# nRF24L01-Chip-v12.net
KiCad netlist of a schematic drawn in EAGLE
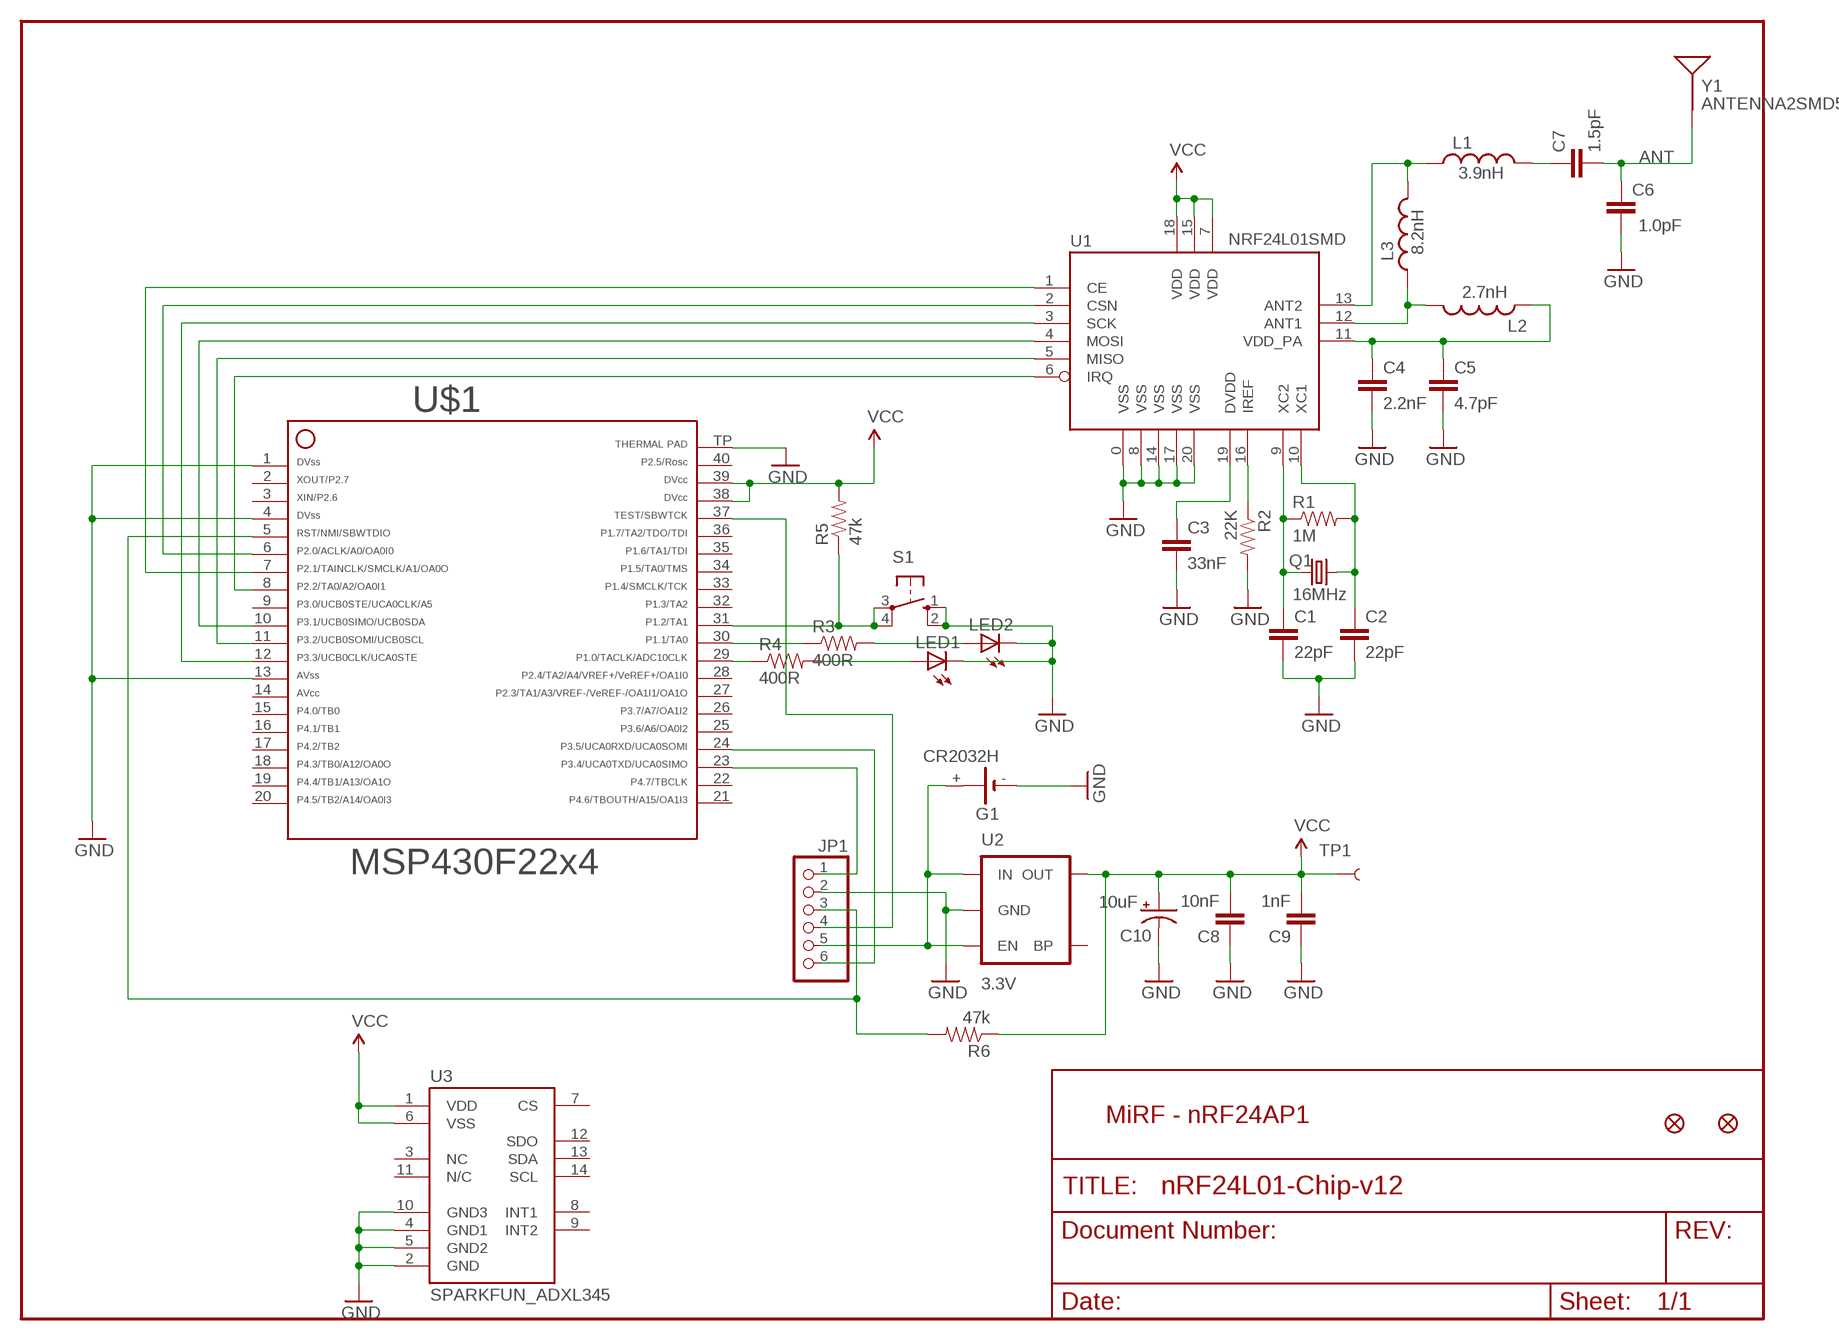
[diagram p0: schematic, sheet 1]

(export (version "E")
  (design (tool "Eeschema 10.0.6"))
  (components
    (comp (ref "C1")
      (value "22pF")
      (footprint "eagle-import:C0402")
      (libsource (lib "eagle-import") (part "CAP0402"))
    )
    (comp (ref "C2")
      (value "22pF")
      (footprint "eagle-import:C0402")
      (libsource (lib "eagle-import") (part "CAP0402"))
    )
    (comp (ref "C3")
      (value "33nF")
      (footprint "eagle-import:C0402")
      (libsource (lib "eagle-import") (part "CAP0402"))
    )
    (comp (ref "C4")
      (value "2.2nF")
      (footprint "eagle-import:C0402")
      (libsource (lib "eagle-import") (part "CAP0402"))
    )
    (comp (ref "C5")
      (value "4.7pF")
      (footprint "eagle-import:C0402")
      (libsource (lib "eagle-import") (part "CAP0402"))
    )
    (comp (ref "C6")
      (value "1.0pF")
      (footprint "eagle-import:C0402")
      (libsource (lib "eagle-import") (part "CAP0402"))
    )
    (comp (ref "C7")
      (value "1.5pF")
      (footprint "eagle-import:C0402")
      (libsource (lib "eagle-import") (part "CAP0402"))
    )
    (comp (ref "C8")
      (value "10nF")
      (footprint "eagle-import:C0402")
      (libsource (lib "eagle-import") (part "CAP0402"))
    )
    (comp (ref "C9")
      (value "1nF")
      (footprint "eagle-import:C0402")
      (libsource (lib "eagle-import") (part "CAP0402"))
    )
    (comp (ref "C10")
      (value "10uF")
      (footprint "eagle-import:EIA3216")
      (libsource (lib "eagle-import") (part "CAP_POL1206"))
    )
    (comp (ref "G1")
      (value "CR2032H")
      (footprint "eagle-import:CR2032H")
      (libsource (lib "eagle-import") (part "CR2032H"))
    )
    (comp (ref "JP1")
      (value "PINHD-1X6")
      (footprint "eagle-import:1X06")
      (libsource (lib "eagle-import") (part "PINHD-1X6"))
    )
    (comp (ref "L1")
      (value "3.9nH")
      (footprint "eagle-import:C0402")
      (libsource (lib "eagle-import") (part "INDUCTOR0402"))
    )
    (comp (ref "L2")
      (value "2.7nH")
      (footprint "eagle-import:C0402")
      (libsource (lib "eagle-import") (part "INDUCTOR0402"))
    )
    (comp (ref "L3")
      (value "8.2nH")
      (footprint "eagle-import:C0402")
      (libsource (lib "eagle-import") (part "INDUCTOR0402"))
    )
    (comp (ref "LED1")
      (value "LEDCHIPLED_0805")
      (footprint "eagle-import:CHIPLED_0805")
      (libsource (lib "eagle-import") (part "LEDCHIPLED_0805"))
    )
    (comp (ref "LED2")
      (value "LEDCHIPLED_0805")
      (footprint "eagle-import:CHIPLED_0805")
      (libsource (lib "eagle-import") (part "LEDCHIPLED_0805"))
    )
    (comp (ref "Q1")
      (value "16MHz")
      (footprint "eagle-import:CRYSTAL-SMD-5X3")
      (libsource (lib "eagle-import") (part "CRYSTAL5X3"))
    )
    (comp (ref "R1")
      (value "1M")
      (footprint "eagle-import:C0402")
      (libsource (lib "eagle-import") (part "RESISTOR0402"))
    )
    (comp (ref "R2")
      (value "22K")
      (footprint "eagle-import:C0402")
      (libsource (lib "eagle-import") (part "RESISTOR0402"))
    )
    (comp (ref "R3")
      (value "400R")
      (footprint "eagle-import:C0402")
      (libsource (lib "eagle-import") (part "RESISTOR0402"))
    )
    (comp (ref "R4")
      (value "400R")
      (footprint "eagle-import:C0402")
      (libsource (lib "eagle-import") (part "RESISTOR0402"))
    )
    (comp (ref "R5")
      (value "47k")
      (footprint "eagle-import:C0402")
      (libsource (lib "eagle-import") (part "RESISTOR0402"))
    )
    (comp (ref "R6")
      (value "47k")
      (footprint "eagle-import:C0402")
      (libsource (lib "eagle-import") (part "RESISTOR0402"))
    )
    (comp (ref "S1")
      (value "10-XX")
      (footprint "eagle-import:B3F-10XX")
      (fields (field (name "MPN") "B3F-1000"))
      (libsource (lib "eagle-import") (part "10-XX"))
    )
    (comp (ref "TP1")
      (value "TEST-POINT3X5")
      (footprint "eagle-import:PAD.03X.05")
      (libsource (lib "eagle-import") (part "TEST-POINT3X5"))
    )
    (comp (ref "U$1")
      (value "F22X4---RHA40")
      (footprint "eagle-import:RHA40")
      (libsource (lib "eagle-import") (part "F22X4---RHA40"))
    )
    (comp (ref "U$2")
      (value "FIDUCIAL1X2")
      (footprint "eagle-import:FIDUCIAL-1X2")
      (libsource (lib "eagle-import") (part "FIDUCIAL1X2"))
    )
    (comp (ref "U$3")
      (value "FIDUCIAL1X2")
      (footprint "eagle-import:FIDUCIAL-1X2")
      (libsource (lib "eagle-import") (part "FIDUCIAL1X2"))
    )
    (comp (ref "U1")
      (value "NRF24L01SMD")
      (footprint "eagle-import:QFN20")
      (libsource (lib "eagle-import") (part "NRF24L01SMD"))
    )
    (comp (ref "U2")
      (value "3.3V")
      (footprint "eagle-import:SOT23-5")
      (libsource (lib "eagle-import") (part "V_REG_LDOSMD"))
    )
    (comp (ref "U3")
      (value "SPARKFUN_ADXL345")
      (footprint "eagle-import:SPARKFUN_LGA14")
      (libsource (lib "eagle-import") (part "SPARKFUN_ADXL345"))
    )
    (comp (ref "Y1")
      (value "ANTENNA2SMD5")
      (footprint "eagle-import:ANTENNA-CHIP5")
      (libsource (lib "eagle-import") (part "ANTENNA2SMD5"))
    )
  )
  (nets
    (net (code "1") (name "/14") (class "Default")
      (node (ref "U$1") (pin "14") (pinfunction "14_14") (pintype "power_in"))
    )
    (net (code "2") (name "/ANT") (class "Default")
      (node (ref "C6") (pin "2") (pinfunction "2_2") (pintype "passive"))
      (node (ref "C7") (pin "2") (pinfunction "2_2") (pintype "passive"))
      (node (ref "Y1") (pin "FEED") (pinfunction "SIGNAL_FEED") (pintype "bidirectional"))
    )
    (net (code "3") (name "GND") (class "Default")
      (node (ref "C1") (pin "2") (pinfunction "2_2") (pintype "passive"))
      (node (ref "C10") (pin "C") (pinfunction "-_C") (pintype "passive"))
      (node (ref "C2") (pin "2") (pinfunction "2_2") (pintype "passive"))
      (node (ref "C3") (pin "2") (pinfunction "2_2") (pintype "passive"))
      (node (ref "C4") (pin "2") (pinfunction "2_2") (pintype "passive"))
      (node (ref "C5") (pin "2") (pinfunction "2_2") (pintype "passive"))
      (node (ref "C6") (pin "1") (pinfunction "1_1") (pintype "passive"))
      (node (ref "C8") (pin "1") (pinfunction "1_1") (pintype "passive"))
      (node (ref "C9") (pin "1") (pinfunction "1_1") (pintype "passive"))
      (node (ref "G1") (pin "-") (pinfunction "-_-") (pintype "passive"))
      (node (ref "JP1") (pin "2") (pinfunction "2_2") (pintype "passive"))
      (node (ref "LED1") (pin "C") (pinfunction "C_C") (pintype "passive"))
      (node (ref "LED2") (pin "C") (pinfunction "C_C") (pintype "passive"))
      (node (ref "R2") (pin "2") (pinfunction "2_2") (pintype "passive"))
      (node (ref "S1") (pin "1") (pinfunction "S_1") (pintype "passive"))
      (node (ref "S1") (pin "2") (pinfunction "S1_2") (pintype "passive"))
      (node (ref "U$1") (pin "1") (pinfunction "1_1") (pintype "power_in"))
      (node (ref "U$1") (pin "13") (pinfunction "13_13") (pintype "power_in"))
      (node (ref "U$1") (pin "4") (pinfunction "4_4") (pintype "power_in"))
      (node (ref "U$1") (pin "TP") (pinfunction "TP_TP") (pintype "power_in"))
      (node (ref "U1") (pin "0") (pinfunction "VSS_0") (pintype "power_in"))
      (node (ref "U1") (pin "14") (pinfunction "VSS_14") (pintype "power_in"))
      (node (ref "U1") (pin "17") (pinfunction "VSS_17") (pintype "power_in"))
      (node (ref "U1") (pin "20") (pinfunction "VSS_20") (pintype "power_in"))
      (node (ref "U1") (pin "8") (pinfunction "VSS_8") (pintype "power_in"))
      (node (ref "U2") (pin "2") (pinfunction "GND_2") (pintype "input"))
      (node (ref "U3") (pin "10") (pinfunction "GND3_10") (pintype "bidirectional"))
      (node (ref "U3") (pin "2") (pinfunction "GND_2") (pintype "bidirectional"))
      (node (ref "U3") (pin "4") (pinfunction "GND1_4") (pintype "bidirectional"))
      (node (ref "U3") (pin "5") (pinfunction "GND2_5") (pintype "bidirectional"))
    )
    (net (code "4") (name "Net-(C7-Pad1)") (class "Default")
      (node (ref "C7") (pin "1") (pinfunction "1_1") (pintype "passive"))
      (node (ref "L1") (pin "2") (pinfunction "2_2") (pintype "passive"))
    )
    (net (code "5") (name "Net-(JP1-Pad1)") (class "Default")
      (node (ref "JP1") (pin "1") (pinfunction "1_1") (pintype "passive"))
      (node (ref "U$1") (pin "23") (pinfunction "23_23") (pintype "bidirectional"))
    )
    (net (code "6") (name "Net-(JP1-Pad3)") (class "Default")
      (node (ref "JP1") (pin "3") (pinfunction "3_3") (pintype "passive"))
      (node (ref "R6") (pin "2") (pinfunction "2_2") (pintype "passive"))
      (node (ref "U$1") (pin "5") (pinfunction "5_5") (pintype "bidirectional"))
    )
    (net (code "7") (name "Net-(JP1-Pad4)") (class "Default")
      (node (ref "JP1") (pin "4") (pinfunction "4_4") (pintype "passive"))
      (node (ref "U$1") (pin "37") (pinfunction "37_37") (pintype "input"))
    )
    (net (code "8") (name "Net-(JP1-Pad6)") (class "Default")
      (node (ref "JP1") (pin "6") (pinfunction "6_6") (pintype "passive"))
      (node (ref "U$1") (pin "24") (pinfunction "24_24") (pintype "bidirectional"))
    )
    (net (code "9") (name "Net-(LED1-PadA)") (class "Default")
      (node (ref "LED1") (pin "A") (pinfunction "A_A") (pintype "passive"))
      (node (ref "R4") (pin "2") (pinfunction "2_2") (pintype "passive"))
    )
    (net (code "10") (name "Net-(LED2-PadA)") (class "Default")
      (node (ref "LED2") (pin "A") (pinfunction "A_A") (pintype "passive"))
      (node (ref "R3") (pin "2") (pinfunction "2_2") (pintype "passive"))
    )
    (net (code "11") (name "Net-(Q1-2)") (class "Default")
      (node (ref "C2") (pin "1") (pinfunction "1_1") (pintype "passive"))
      (node (ref "Q1") (pin "3") (pinfunction "2_3") (pintype "passive"))
      (node (ref "R1") (pin "2") (pinfunction "2_2") (pintype "passive"))
      (node (ref "U1") (pin "10") (pinfunction "XC1_10") (pintype "input"))
    )
    (net (code "12") (name "Net-(R3-Pad1)") (class "Default")
      (node (ref "R3") (pin "1") (pinfunction "1_1") (pintype "passive"))
      (node (ref "U$1") (pin "30") (pinfunction "30_30") (pintype "bidirectional"))
    )
    (net (code "13") (name "Net-(R4-Pad1)") (class "Default")
      (node (ref "R4") (pin "1") (pinfunction "1_1") (pintype "passive"))
      (node (ref "U$1") (pin "29") (pinfunction "29_29") (pintype "bidirectional"))
    )
    (net (code "14") (name "Net-(S1-P)") (class "Default")
      (node (ref "R5") (pin "1") (pinfunction "1_1") (pintype "passive"))
      (node (ref "S1") (pin "3") (pinfunction "P_3") (pintype "passive"))
      (node (ref "S1") (pin "4") (pinfunction "P1_4") (pintype "passive"))
      (node (ref "U$1") (pin "31") (pinfunction "31_31") (pintype "bidirectional"))
    )
    (net (code "15") (name "Net-(U1-ANT1)") (class "Default")
      (node (ref "L2") (pin "2") (pinfunction "2_2") (pintype "passive"))
      (node (ref "L3") (pin "1") (pinfunction "1_1") (pintype "passive"))
      (node (ref "U1") (pin "12") (pinfunction "ANT1_12") (pintype "output"))
    )
    (net (code "16") (name "Net-(U1-ANT2)") (class "Default")
      (node (ref "L1") (pin "1") (pinfunction "1_1") (pintype "passive"))
      (node (ref "L3") (pin "2") (pinfunction "2_2") (pintype "passive"))
      (node (ref "U1") (pin "13") (pinfunction "ANT2_13") (pintype "output"))
    )
    (net (code "17") (name "Net-(U1-CE)") (class "Default")
      (node (ref "U$1") (pin "7") (pinfunction "7_7") (pintype "bidirectional"))
      (node (ref "U1") (pin "1") (pinfunction "CE_1") (pintype "input"))
    )
    (net (code "18") (name "Net-(U1-CSN)") (class "Default")
      (node (ref "U$1") (pin "6") (pinfunction "6_6") (pintype "bidirectional"))
      (node (ref "U1") (pin "2") (pinfunction "CSN_2") (pintype "input"))
    )
    (net (code "19") (name "Net-(U1-DVDD)") (class "Default")
      (node (ref "C3") (pin "1") (pinfunction "1_1") (pintype "passive"))
      (node (ref "U1") (pin "19") (pinfunction "DVDD_19") (pintype "power_in"))
    )
    (net (code "20") (name "Net-(U1-IREF)") (class "Default")
      (node (ref "R2") (pin "1") (pinfunction "1_1") (pintype "passive"))
      (node (ref "U1") (pin "16") (pinfunction "IREF_16") (pintype "input"))
    )
    (net (code "21") (name "Net-(U1-IRQ)") (class "Default")
      (node (ref "U$1") (pin "8") (pinfunction "8_8") (pintype "bidirectional"))
      (node (ref "U1") (pin "6") (pinfunction "IRQ_6") (pintype "output"))
    )
    (net (code "22") (name "Net-(U1-MISO)") (class "Default")
      (node (ref "U$1") (pin "11") (pinfunction "11_11") (pintype "bidirectional"))
      (node (ref "U1") (pin "5") (pinfunction "MISO_5") (pintype "output"))
    )
    (net (code "23") (name "Net-(U1-MOSI)") (class "Default")
      (node (ref "U$1") (pin "10") (pinfunction "10_10") (pintype "bidirectional"))
      (node (ref "U1") (pin "4") (pinfunction "MOSI_4") (pintype "input"))
    )
    (net (code "24") (name "Net-(U1-SCK)") (class "Default")
      (node (ref "U$1") (pin "12") (pinfunction "12_12") (pintype "bidirectional"))
      (node (ref "U1") (pin "3") (pinfunction "SCK_3") (pintype "input"))
    )
    (net (code "25") (name "Net-(U1-VDD_PA)") (class "Default")
      (node (ref "C4") (pin "1") (pinfunction "1_1") (pintype "passive"))
      (node (ref "C5") (pin "1") (pinfunction "1_1") (pintype "passive"))
      (node (ref "L2") (pin "1") (pinfunction "1_1") (pintype "passive"))
      (node (ref "U1") (pin "11") (pinfunction "VDD_PA_11") (pintype "power_in"))
    )
    (net (code "26") (name "Net-(U1-XC2)") (class "Default")
      (node (ref "C1") (pin "1") (pinfunction "1_1") (pintype "passive"))
      (node (ref "Q1") (pin "1") (pinfunction "1_1") (pintype "passive"))
      (node (ref "R1") (pin "1") (pinfunction "1_1") (pintype "passive"))
      (node (ref "U1") (pin "9") (pinfunction "XC2_9") (pintype "input"))
    )
    (net (code "27") (name "Net-(U2-EN)") (class "Default")
      (node (ref "G1") (pin "+") (pinfunction "+_+") (pintype "passive"))
      (node (ref "JP1") (pin "5") (pinfunction "5_5") (pintype "passive"))
      (node (ref "U2") (pin "1") (pinfunction "IN_1") (pintype "input"))
      (node (ref "U2") (pin "3") (pinfunction "EN_3") (pintype "input"))
    )
    (net (code "28") (name "VCC") (class "Default")
      (node (ref "C10") (pin "A") (pinfunction "+_A") (pintype "passive"))
      (node (ref "C8") (pin "2") (pinfunction "2_2") (pintype "passive"))
      (node (ref "C9") (pin "2") (pinfunction "2_2") (pintype "passive"))
      (node (ref "R5") (pin "2") (pinfunction "2_2") (pintype "passive"))
      (node (ref "R6") (pin "1") (pinfunction "1_1") (pintype "passive"))
      (node (ref "TP1") (pin "P$1") (pinfunction "1_P$1") (pintype "bidirectional"))
      (node (ref "U$1") (pin "38") (pinfunction "38_38") (pintype "power_in"))
      (node (ref "U$1") (pin "39") (pinfunction "39_39") (pintype "power_in"))
      (node (ref "U1") (pin "15") (pinfunction "VDD_15") (pintype "power_in"))
      (node (ref "U1") (pin "18") (pinfunction "VDD_18") (pintype "power_in"))
      (node (ref "U1") (pin "7") (pinfunction "VDD_7") (pintype "power_in"))
      (node (ref "U2") (pin "5") (pinfunction "OUT_5") (pintype "passive"))
      (node (ref "U3") (pin "1") (pinfunction "VDD_1") (pintype "bidirectional"))
      (node (ref "U3") (pin "6") (pinfunction "VSS_6") (pintype "bidirectional"))
    )
    (net (code "29") (name "unconnected-(G1-+-Pad+@1)") (class "Default")
      (node (ref "G1") (pin "+@1") (pinfunction "+_+@1") (pintype "passive"))
    )
    (net (code "30") (name "unconnected-(U$1-Pad2)") (class "Default")
      (node (ref "U$1") (pin "2") (pinfunction "2_2") (pintype "bidirectional"))
    )
    (net (code "31") (name "unconnected-(U$1-Pad3)") (class "Default")
      (node (ref "U$1") (pin "3") (pinfunction "3_3") (pintype "bidirectional"))
    )
    (net (code "32") (name "unconnected-(U$1-Pad9)") (class "Default")
      (node (ref "U$1") (pin "9") (pinfunction "9_9") (pintype "bidirectional"))
    )
    (net (code "33") (name "unconnected-(U$1-Pad15)") (class "Default")
      (node (ref "U$1") (pin "15") (pinfunction "15_15") (pintype "bidirectional"))
    )
    (net (code "34") (name "unconnected-(U$1-Pad16)") (class "Default")
      (node (ref "U$1") (pin "16") (pinfunction "16_16") (pintype "bidirectional"))
    )
    (net (code "35") (name "unconnected-(U$1-Pad17)") (class "Default")
      (node (ref "U$1") (pin "17") (pinfunction "17_17") (pintype "bidirectional"))
    )
    (net (code "36") (name "unconnected-(U$1-Pad18)") (class "Default")
      (node (ref "U$1") (pin "18") (pinfunction "18_18") (pintype "bidirectional"))
    )
    (net (code "37") (name "unconnected-(U$1-Pad19)") (class "Default")
      (node (ref "U$1") (pin "19") (pinfunction "19_19") (pintype "bidirectional"))
    )
    (net (code "38") (name "unconnected-(U$1-Pad20)") (class "Default")
      (node (ref "U$1") (pin "20") (pinfunction "20_20") (pintype "bidirectional"))
    )
    (net (code "39") (name "unconnected-(U$1-Pad21)") (class "Default")
      (node (ref "U$1") (pin "21") (pinfunction "21_21") (pintype "bidirectional"))
    )
    (net (code "40") (name "unconnected-(U$1-Pad22)") (class "Default")
      (node (ref "U$1") (pin "22") (pinfunction "22_22") (pintype "bidirectional"))
    )
    (net (code "41") (name "unconnected-(U$1-Pad25)") (class "Default")
      (node (ref "U$1") (pin "25") (pinfunction "25_25") (pintype "bidirectional"))
    )
    (net (code "42") (name "unconnected-(U$1-Pad26)") (class "Default")
      (node (ref "U$1") (pin "26") (pinfunction "26_26") (pintype "bidirectional"))
    )
    (net (code "43") (name "unconnected-(U$1-Pad27)") (class "Default")
      (node (ref "U$1") (pin "27") (pinfunction "27_27") (pintype "bidirectional"))
    )
    (net (code "44") (name "unconnected-(U$1-Pad28)") (class "Default")
      (node (ref "U$1") (pin "28") (pinfunction "28_28") (pintype "bidirectional"))
    )
    (net (code "45") (name "unconnected-(U$1-Pad32)") (class "Default")
      (node (ref "U$1") (pin "32") (pinfunction "32_32") (pintype "bidirectional"))
    )
    (net (code "46") (name "unconnected-(U$1-Pad33)") (class "Default")
      (node (ref "U$1") (pin "33") (pinfunction "33_33") (pintype "bidirectional"))
    )
    (net (code "47") (name "unconnected-(U$1-Pad34)") (class "Default")
      (node (ref "U$1") (pin "34") (pinfunction "34_34") (pintype "bidirectional"))
    )
    (net (code "48") (name "unconnected-(U$1-Pad35)") (class "Default")
      (node (ref "U$1") (pin "35") (pinfunction "35_35") (pintype "bidirectional"))
    )
    (net (code "49") (name "unconnected-(U$1-Pad36)") (class "Default")
      (node (ref "U$1") (pin "36") (pinfunction "36_36") (pintype "bidirectional"))
    )
    (net (code "50") (name "unconnected-(U$1-Pad40)") (class "Default")
      (node (ref "U$1") (pin "40") (pinfunction "40_40") (pintype "bidirectional"))
    )
    (net (code "51") (name "unconnected-(U2-BP-Pad4)") (class "Default")
      (node (ref "U2") (pin "4") (pinfunction "BP_4") (pintype "input"))
    )
    (net (code "52") (name "unconnected-(U3-CS-Pad7)") (class "Default")
      (node (ref "U3") (pin "7") (pinfunction "CS_7") (pintype "bidirectional"))
    )
    (net (code "53") (name "unconnected-(U3-INT1-Pad8)") (class "Default")
      (node (ref "U3") (pin "8") (pinfunction "INT1_8") (pintype "bidirectional"))
    )
    (net (code "54") (name "unconnected-(U3-INT2-Pad9)") (class "Default")
      (node (ref "U3") (pin "9") (pinfunction "INT2_9") (pintype "bidirectional"))
    )
    (net (code "55") (name "unconnected-(U3-NC-Pad3)") (class "Default")
      (node (ref "U3") (pin "3") (pinfunction "NC_3") (pintype "bidirectional"))
    )
    (net (code "56") (name "unconnected-(U3-N{slash}C-Pad11)") (class "Default")
      (node (ref "U3") (pin "11") (pinfunction "N/C_11") (pintype "bidirectional"))
    )
    (net (code "57") (name "unconnected-(U3-SCL-Pad14)") (class "Default")
      (node (ref "U3") (pin "14") (pinfunction "SCL_14") (pintype "bidirectional"))
    )
    (net (code "58") (name "unconnected-(U3-SDA-Pad13)") (class "Default")
      (node (ref "U3") (pin "13") (pinfunction "SDA_13") (pintype "bidirectional"))
    )
    (net (code "59") (name "unconnected-(U3-SDO-Pad12)") (class "Default")
      (node (ref "U3") (pin "12") (pinfunction "SDO_12") (pintype "bidirectional"))
    )
  )
)
